# MCU_Peripherals.net
KiCad netlist of a schematic drawn in Altium Designer
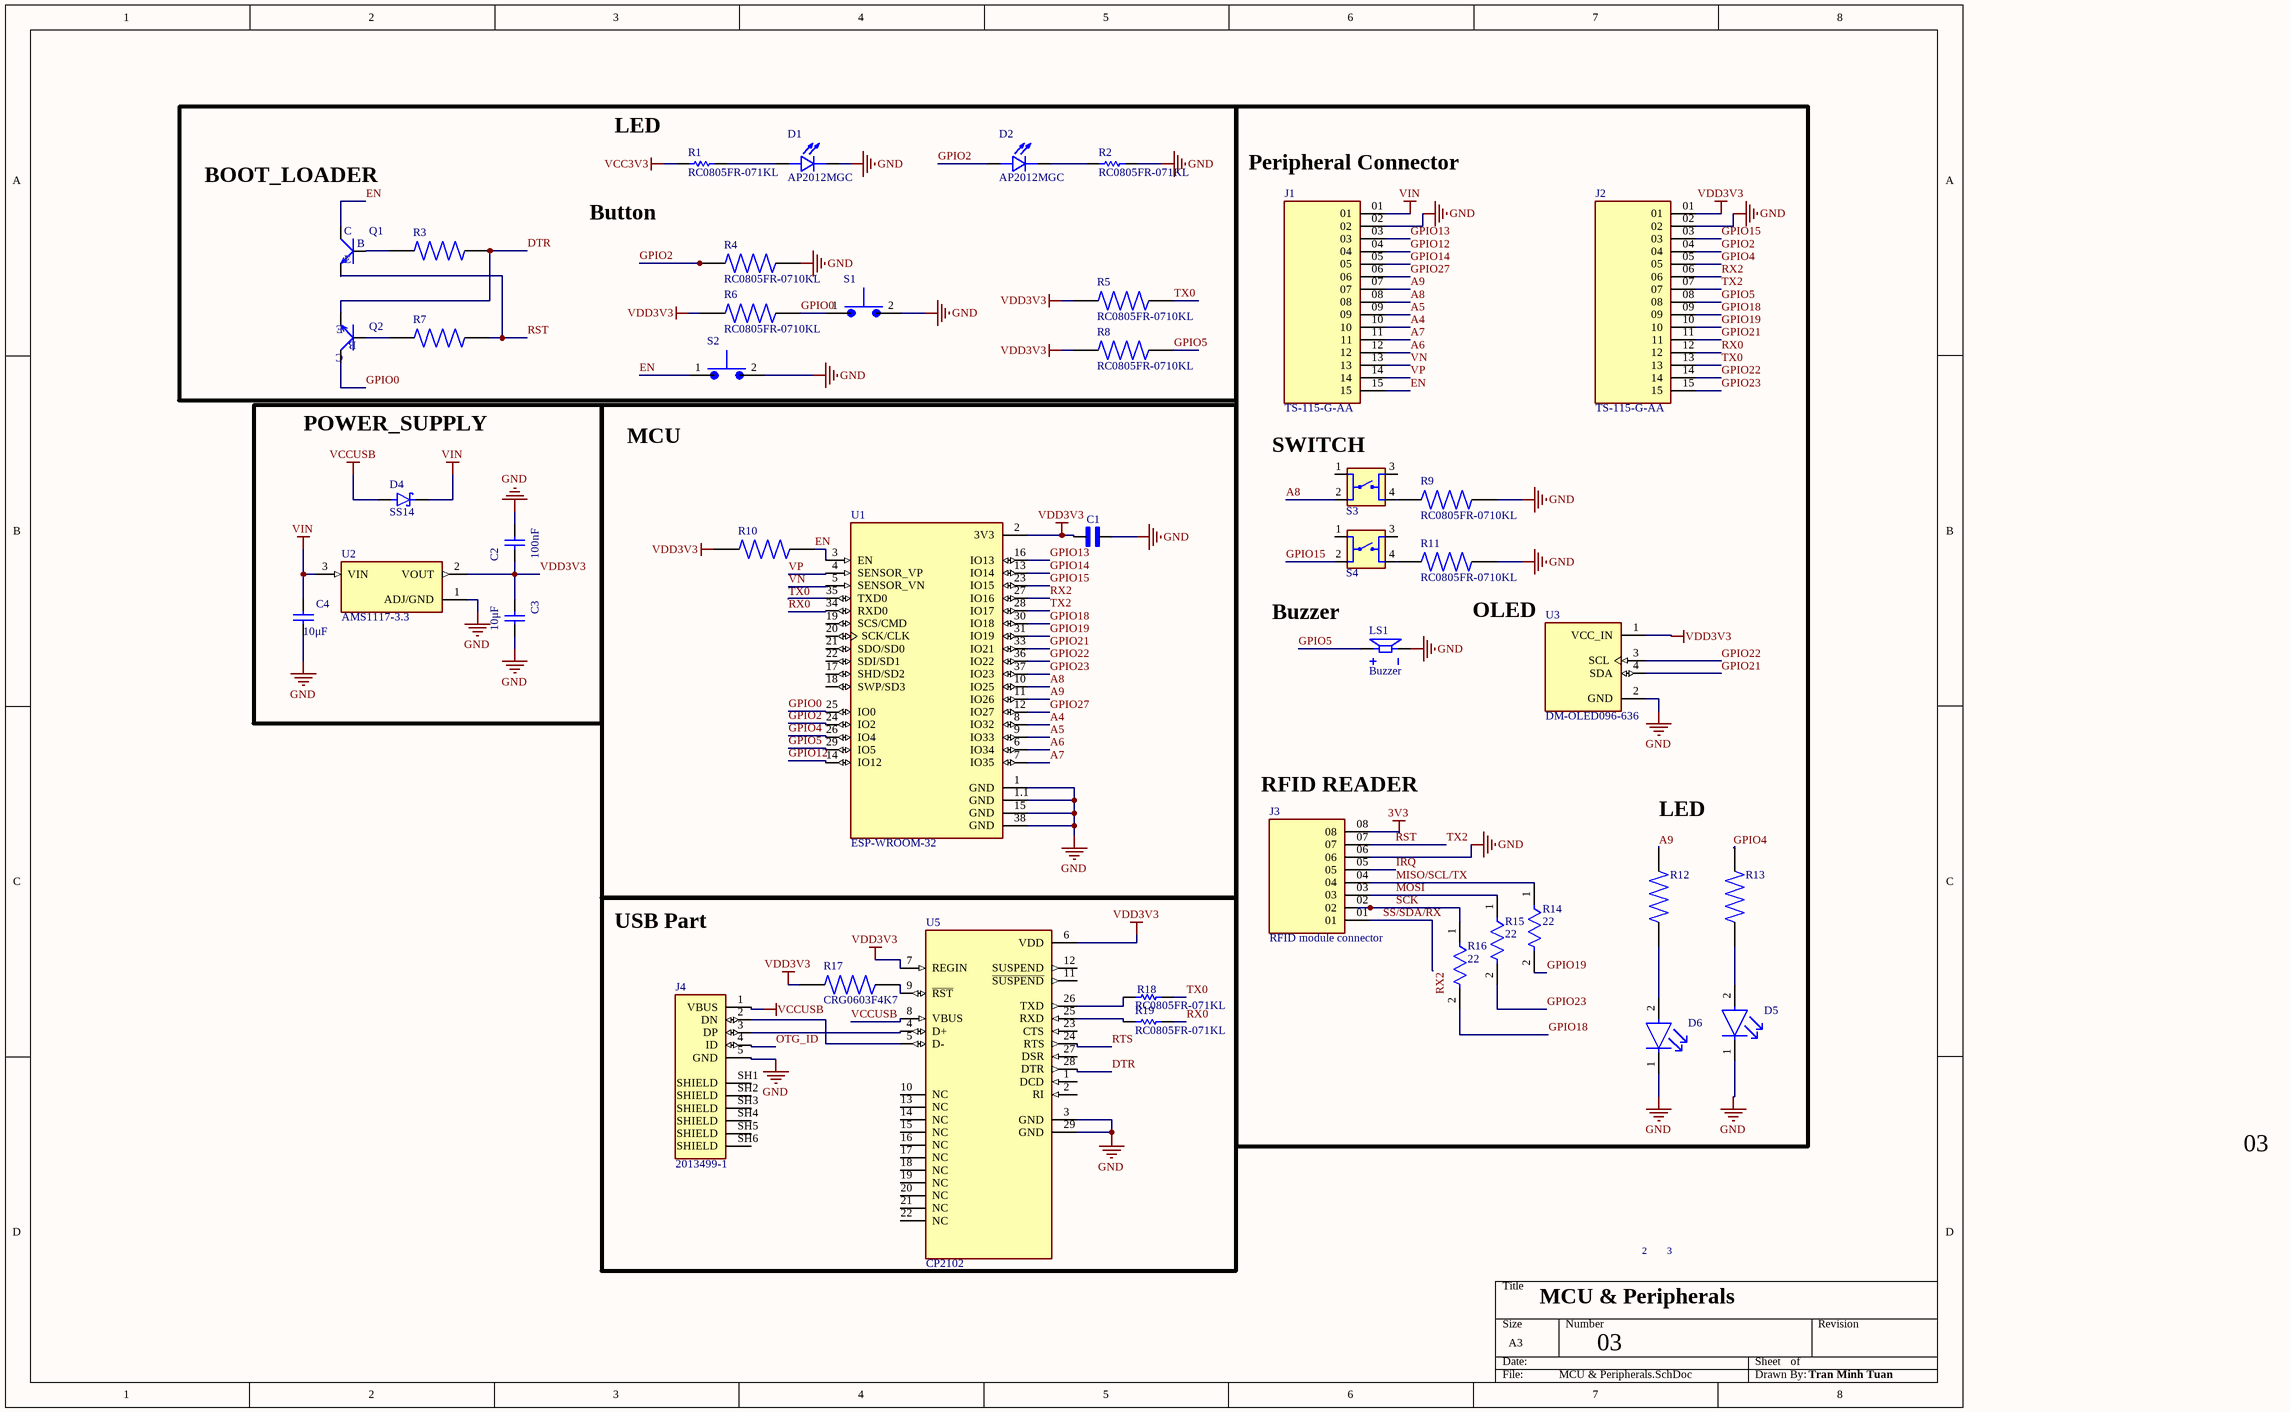
[diagram p0: MCU & Peripherals.SchDoc]

(export (version "E")
  (design (tool "Eeschema 10.0.6"))
  (components
    (comp (ref "C1")
      (value "GRM32EC70J107ME15L")
      (footprint "CAPC3225X270N")
      (description "SMD capacitor X7S(EIA) with capacitance 100uF Tol.20%. Rated voltage 6.3Vdc 125C")
      (fields (field (name "MF") "Murata Electronics"))
      (libsource (lib "Cap100uF") (part "GRM32EC70J107ME15L"))
    )
    (comp (ref "C2")
      (value "100nF")
      (footprint "WCAP-CSGP_0805_L2W1.25H0.8_Reflow")
      (description "WCAP-CSGP Multilayer Ceramic Chip Capacitor, General Purpose, size 0805, X7R, 100nF, 25V")
      (fields
        (field (name "MANUFACTURER PART NUMBER") "885012207072")
        (field (name "MANUFACTURER") "Wurth Elektronik")
      )
      (libsource (lib "Cap100n") (part "885012207072"))
    )
    (comp (ref "C3")
      (value "10μF")
      (footprint "WCAP-CSGP_0805_L2W1.25H1.25")
      (description "WCAP-CSGP Multilayer Ceramic Chip Capacitor, General Purpose, size 0805, X5R Class II, 10μF, 25V")
      (fields
        (field (name "MANUFACTURER PART NUMBER") "885012107027")
        (field (name "MANUFACTURER") "Wurth Elektronik")
      )
      (libsource (lib "Cap100n") (part "885012107027"))
    )
    (comp (ref "C4")
      (value "10μF")
      (footprint "WCAP-CSGP_0805_L2W1.25H1.25")
      (description "WCAP-CSGP Multilayer Ceramic Chip Capacitor, General Purpose, size 0805, X5R Class II, 10μF, 25V")
      (fields
        (field (name "MANUFACTURER PART NUMBER") "885012107027")
        (field (name "MANUFACTURER") "Wurth Elektronik")
      )
      (libsource (lib "Cap100n") (part "885012107027"))
    )
    (comp (ref "D1")
      (value "AP2012MGC")
      (footprint "LED_AP2012MGC")
      (description "Green 2 x 1.25 x 1.1 mm 120Â° Water Clear 70 mcd 2.1 V Chip LED Lamp SMT")
      (fields (field (name "MF") "Kingbright"))
      (libsource (lib "LED_GREEN") (part "AP2012MGC"))
    )
    (comp (ref "D2")
      (value "AP2012MGC")
      (footprint "LED_AP2012MGC")
      (description "Green 2 x 1.25 x 1.1 mm 120Â° Water Clear 70 mcd 2.1 V Chip LED Lamp SMT")
      (fields (field (name "MF") "Kingbright"))
      (libsource (lib "LED_GREEN") (part "AP2012MGC"))
    )
    (comp (ref "D4")
      (value "SS14")
      (footprint "DIOM4325X250N")
      (description "1A, 40V, Schottky Rectifier")
      (fields (field (name "MF") "Taiwan Semiconductor"))
      (libsource (lib "SS14") (part "SS14"))
    )
    (comp (ref "D5")
      (value "HLMP-1719")
      (footprint "FP-HLMP-1719-MFG")
      (description "LED YELLOW DIFFUSED T-1 T/H")
      (fields
        (field (name "MANUFACTURER") "Broadcom")
        (field (name "OCTOPART") "https://octopart.com/hlmp-1719-broadcom-71130405")
      )
      (libsource (lib "LED") (part "CMP-2000-06410-2"))
    )
    (comp (ref "D6")
      (value "HLMP-1719")
      (footprint "FP-HLMP-1719-MFG")
      (description "LED YELLOW DIFFUSED T-1 T/H")
      (fields
        (field (name "MANUFACTURER") "Broadcom")
        (field (name "OCTOPART") "https://octopart.com/hlmp-1719-broadcom-71130405")
      )
      (libsource (lib "LED") (part "CMP-2000-06410-2"))
    )
    (comp (ref "J1")
      (value "TS-115-G-AA")
      (footprint "SAMTEC_TS-115-G-AA")
      (fields (field (name "MF") "Samtec"))
      (libsource (lib "15x1 pin") (part "TS-115-G-AA"))
    )
    (comp (ref "J2")
      (value "TS-115-G-AA")
      (footprint "SAMTEC_TS-115-G-AA")
      (fields (field (name "MF") "Samtec"))
      (libsource (lib "15x1 pin") (part "TS-115-G-AA"))
    )
    (comp (ref "J3")
      (value "RFID module connector")
      (footprint "SAMTEC_SL-108-T-19")
      (fields (field (name "MP") "SL-108-T-19"))
      (libsource (lib "8 position connector") (part "SL-108-T-19"))
    )
    (comp (ref "J4")
      (value "2013499-1")
      (footprint "TE_2013499-1")
      (libsource (lib "Micro_USB") (part "2013499-1"))
    )
    (comp (ref "LS1")
      (value "Buzzer")
      (footprint "XDCR_CMI-1210-5-95T")
      (fields (field (name "MP") "CMI-1210-5-95T"))
      (libsource (lib "CMI-1210-5-95T") (part "CMI-1210-5-95T"))
    )
    (comp (ref "Q1")
      (value "SMD-TRANSISTORS-NPN-25V-500MW(SOT-23)")
      (footprint "SOT-23")
      (description "Bipolar (BJT) Transistor NPN 25 V 500 mA 150MHz 300 mW Surface Mount SOT-23")
      (fields (field (name "MF") "UMW") (field (name "MP") "S8050"))
      (libsource (lib "S8050") (part "SMD-TRANSISTORS-NPN-25V-500MW(SOT-23)"))
    )
    (comp (ref "Q2")
      (value "SMD-TRANSISTORS-NPN-25V-500MW(SOT-23)")
      (footprint "SOT-23")
      (description "Bipolar (BJT) Transistor NPN 25 V 500 mA 150MHz 300 mW Surface Mount SOT-23")
      (fields (field (name "MF") "UMW") (field (name "MP") "S8050"))
      (libsource (lib "S8050") (part "SMD-TRANSISTORS-NPN-25V-500MW(SOT-23)"))
    )
    (comp (ref "R1")
      (value "RC0805FR-071KL")
      (footprint "RESC2013X60X35NL10T20")
      (description "Chip Resistor, 1 KOhm, +/- 1%, 125 mW, -55 to 155 degC, 0805 (2012 Metric), RoHS, Tape and Reel")
      (fields (field (name "TOLERANCE") "1%") (field (name "MANUFACTURER") "Yageo"))
      (libsource (lib "RES1K") (part "CMP-2100-03671-1"))
    )
    (comp (ref "R2")
      (value "RC0805FR-071KL")
      (footprint "RESC2013X60X35NL10T20")
      (description "Chip Resistor, 1 KOhm, +/- 1%, 125 mW, -55 to 155 degC, 0805 (2012 Metric), RoHS, Tape and Reel")
      (fields (field (name "TOLERANCE") "1%") (field (name "MANUFACTURER") "Yageo"))
      (libsource (lib "RES1K") (part "CMP-2100-03671-1"))
    )
    (comp (ref "R3")
      (value "RC0805FR-0710KL")
      (footprint "RESC2012X60N")
      (description "10 kOhms Â±1% 0.125W, 1/8W Chip Resistor 0805 (2012 Metric) Moisture Resistant Thick Film")
      (fields (field (name "MF") "Yageo"))
      (libsource (lib "RES10k") (part "RC0805FR-0710KL"))
    )
    (comp (ref "R4")
      (value "RC0805FR-0710KL")
      (footprint "RESC2012X60N")
      (description "10 kOhms Â±1% 0.125W, 1/8W Chip Resistor 0805 (2012 Metric) Moisture Resistant Thick Film")
      (fields (field (name "MF") "Yageo"))
      (libsource (lib "RES10k") (part "RC0805FR-0710KL"))
    )
    (comp (ref "R5")
      (value "RC0805FR-0710KL")
      (footprint "RESC2012X60N")
      (description "10 kOhms Â±1% 0.125W, 1/8W Chip Resistor 0805 (2012 Metric) Moisture Resistant Thick Film")
      (fields (field (name "MF") "Yageo"))
      (libsource (lib "RES10k") (part "RC0805FR-0710KL"))
    )
    (comp (ref "R6")
      (value "RC0805FR-0710KL")
      (footprint "RESC2012X60N")
      (description "10 kOhms Â±1% 0.125W, 1/8W Chip Resistor 0805 (2012 Metric) Moisture Resistant Thick Film")
      (fields (field (name "MF") "Yageo"))
      (libsource (lib "RES10k") (part "RC0805FR-0710KL"))
    )
    (comp (ref "R7")
      (value "RC0805FR-0710KL")
      (footprint "RESC2012X60N")
      (description "10 kOhms Â±1% 0.125W, 1/8W Chip Resistor 0805 (2012 Metric) Moisture Resistant Thick Film")
      (fields (field (name "MF") "Yageo"))
      (libsource (lib "RES10k") (part "RC0805FR-0710KL"))
    )
    (comp (ref "R8")
      (value "RC0805FR-0710KL")
      (footprint "RESC2012X60N")
      (description "10 kOhms Â±1% 0.125W, 1/8W Chip Resistor 0805 (2012 Metric) Moisture Resistant Thick Film")
      (fields (field (name "MF") "Yageo"))
      (libsource (lib "RES10k") (part "RC0805FR-0710KL"))
    )
    (comp (ref "R9")
      (value "RC0805FR-0710KL")
      (footprint "RESC2012X60N")
      (description "10 kOhms Â±1% 0.125W, 1/8W Chip Resistor 0805 (2012 Metric) Moisture Resistant Thick Film")
      (fields (field (name "MF") "Yageo"))
      (libsource (lib "RES10k") (part "RC0805FR-0710KL"))
    )
    (comp (ref "R10")
      (value "RC0805FR-0710KL")
      (footprint "RESC2012X60N")
      (description "10 kOhms Â±1% 0.125W, 1/8W Chip Resistor 0805 (2012 Metric) Moisture Resistant Thick Film")
      (fields (field (name "MF") "Yageo"))
      (libsource (lib "RES10k") (part "RC0805FR-0710KL"))
    )
    (comp (ref "R11")
      (value "RC0805FR-0710KL")
      (footprint "RESC2012X60N")
      (description "10 kOhms Â±1% 0.125W, 1/8W Chip Resistor 0805 (2012 Metric) Moisture Resistant Thick Film")
      (fields (field (name "MF") "Yageo"))
      (libsource (lib "RES10k") (part "RC0805FR-0710KL"))
    )
    (comp (ref "R12")
      (value "ERJPA3F5100V")
      (footprint "RES_ERJPA3F5100V")
      (description "RES, THICK FILM, 510R, 1%, 0.25W, 0603")
      (fields (field (name "MF") "Panasonic") (field (name "MP") "ERJ-PA3F5100V"))
      (libsource (lib "RES510") (part "ERJPA3F5100V"))
    )
    (comp (ref "R13")
      (value "ERJPA3F5100V")
      (footprint "RES_ERJPA3F5100V")
      (description "RES, THICK FILM, 510R, 1%, 0.25W, 0603")
      (fields (field (name "MF") "Panasonic") (field (name "MP") "ERJ-PA3F5100V"))
      (libsource (lib "RES510") (part "ERJPA3F5100V"))
    )
    (comp (ref "R14")
      (value "22")
      (footprint "FP-ERJ3G-MFG")
      (description "RES SMD 22 OHM 5% 1/10W 0603")
      (fields (field (name "TOLERANCE") "5%"))
      (libsource (lib "RES22") (part "CMP-2000-00745-2"))
    )
    (comp (ref "R15")
      (value "22")
      (footprint "FP-ERJ3G-MFG")
      (description "RES SMD 22 OHM 5% 1/10W 0603")
      (fields (field (name "TOLERANCE") "5%"))
      (libsource (lib "RES22") (part "CMP-2000-00745-2"))
    )
    (comp (ref "R16")
      (value "22")
      (footprint "FP-ERJ3G-MFG")
      (description "RES SMD 22 OHM 5% 1/10W 0603")
      (fields (field (name "TOLERANCE") "5%"))
      (libsource (lib "RES22") (part "CMP-2000-00745-2"))
    )
    (comp (ref "R17")
      (value "CRG0603F4K7")
      (footprint "RESC1608X55N")
      (fields (field (name "MF") "TE Connectivity") (field (name "TOLERANCE") "1%"))
      (libsource (lib "RES4.7k") (part "CRG0603F4K7"))
    )
    (comp (ref "R18")
      (value "RC0805FR-071KL")
      (footprint "RESC2013X60X35NL10T20")
      (description "Chip Resistor, 1 KOhm, +/- 1%, 125 mW, -55 to 155 degC, 0805 (2012 Metric), RoHS, Tape and Reel")
      (fields (field (name "TOLERANCE") "1%") (field (name "MANUFACTURER") "Yageo"))
      (libsource (lib "RES1K") (part "CMP-2100-03671-1"))
    )
    (comp (ref "R19")
      (value "RC0805FR-071KL")
      (footprint "RESC2013X60X35NL10T20")
      (description "Chip Resistor, 1 KOhm, +/- 1%, 125 mW, -55 to 155 degC, 0805 (2012 Metric), RoHS, Tape and Reel")
      (fields (field (name "TOLERANCE") "1%") (field (name "MANUFACTURER") "Yageo"))
      (libsource (lib "RES1K") (part "CMP-2100-03671-1"))
    )
    (comp (ref "S1")
      (value "TS10-63-26-BE-250-SMT-TR")
      (footprint "SW_TS10-63-26-BE-250-SMT-TR")
      (description "6.1 x 3.8 mm, 2.6 mm Actuator Height, 250 gf, Surface Mount, SPST, Tactile Switch")
      (fields (field (name "MF") "Same Sky"))
      (libsource (lib "Switch") (part "TS10-63-26-BE-250-SMT-TR"))
    )
    (comp (ref "S2")
      (value "TS10-63-26-BE-250-SMT-TR")
      (footprint "SW_TS10-63-26-BE-250-SMT-TR")
      (description "6.1 x 3.8 mm, 2.6 mm Actuator Height, 250 gf, Surface Mount, SPST, Tactile Switch")
      (fields (field (name "MF") "Same Sky"))
      (libsource (lib "Switch") (part "TS10-63-26-BE-250-SMT-TR"))
    )
    (comp (ref "S3")
      (value "FSM8JH")
      (footprint "SW_FSM8JH")
      (description "Tactile Switch SPST-NO Top Actuated Through Hole")
      (fields (field (name "MF") "TE Connectivity"))
      (libsource (lib "Button") (part "FSM8JH"))
    )
    (comp (ref "S4")
      (value "FSM8JH")
      (footprint "SW_FSM8JH")
      (description "Tactile Switch SPST-NO Top Actuated Through Hole")
      (fields (field (name "MF") "TE Connectivity"))
      (libsource (lib "Button") (part "FSM8JH"))
    )
    (comp (ref "U1")
      (value "ESP-WROOM-32")
      (footprint "MODULE_ESP-WROOM-32")
      (fields (field (name "MF") "Espressif Systems"))
      (libsource (lib "ESP-WROOM-32") (part "ESP-WROOM-32"))
    )
    (comp (ref "U2")
      (value "AMS1117-3.3")
      (footprint "SOT229P700X180-4N")
      (description "Linear Voltage Regulator IC Positive Fixed 1 Output 1A SOT-223-3L")
      (fields (field (name "MF") "UMW"))
      (libsource (lib "AMS1117-3.3") (part "AMS1117-3.3"))
    )
    (comp (ref "U3")
      (value "DM-OLED096-636")
      (footprint "MODULE_DM-OLED096-636")
      (description "0.96â€ 128 X 64 MONOCHROME GRAPHIC OLED DISPLAY MODULE - I2C")
      (fields (field (name "MF") "Display Module"))
      (libsource (lib "DM-OLED096-636") (part "DM-OLED096-636"))
    )
    (comp (ref "U5")
      (value "CP2102")
      (footprint "QFN50P500X500X100-29N")
      (description "CP2102N USB 2.0 to UART (RS232) Bridge Interface Evaluation Board")
      (fields (field (name "MF") "Silicon Labs"))
      (libsource (lib "CP2102") (part "CP2102"))
    )
  )
  (nets
    (net (code "1") (name "/A4") (class "Default")
      (node (ref "J1") (pin "10") (pinfunction "10_10") (pintype "passive"))
      (node (ref "U1") (pin "8") (pinfunction "IO32_8") (pintype "bidirectional"))
    )
    (net (code "2") (name "/A5") (class "Default")
      (node (ref "J1") (pin "09") (pinfunction "09_09") (pintype "passive"))
      (node (ref "U1") (pin "9") (pinfunction "IO33_9") (pintype "bidirectional"))
    )
    (net (code "3") (name "/A6") (class "Default")
      (node (ref "J1") (pin "12") (pinfunction "12_12") (pintype "passive"))
      (node (ref "U1") (pin "6") (pinfunction "IO34_6") (pintype "bidirectional"))
    )
    (net (code "4") (name "/A7") (class "Default")
      (node (ref "J1") (pin "11") (pinfunction "11_11") (pintype "passive"))
      (node (ref "U1") (pin "7") (pinfunction "IO35_7") (pintype "bidirectional"))
    )
    (net (code "5") (name "/A8") (class "Default")
      (node (ref "J1") (pin "08") (pinfunction "08_08") (pintype "passive"))
      (node (ref "S3") (pin "2") (pinfunction "2_2") (pintype "passive"))
      (node (ref "U1") (pin "10") (pinfunction "IO25_10") (pintype "bidirectional"))
    )
    (net (code "6") (name "/A9") (class "Default")
      (node (ref "J1") (pin "07") (pinfunction "07_07") (pintype "passive"))
      (node (ref "R12") (pin "1") (pinfunction "1_1") (pintype "passive"))
      (node (ref "U1") (pin "11") (pinfunction "IO26_11") (pintype "bidirectional"))
    )
    (net (code "7") (name "/DTR") (class "Default")
      (node (ref "Q2") (pin "2") (pinfunction "E_2") (pintype "passive"))
      (node (ref "R3") (pin "2") (pinfunction "2_2") (pintype "passive"))
      (node (ref "U5") (pin "28") (pinfunction "DTR_28") (pintype "output"))
    )
    (net (code "8") (name "/EN") (class "Default")
      (node (ref "J1") (pin "15") (pinfunction "15_15") (pintype "passive"))
      (node (ref "Q1") (pin "3") (pinfunction "C_3") (pintype "passive"))
      (node (ref "R10") (pin "2") (pinfunction "2_2") (pintype "passive"))
      (node (ref "S2") (pin "1") (pinfunction "1_1") (pintype "passive"))
      (node (ref "U1") (pin "3") (pinfunction "EN_3") (pintype "input"))
    )
    (net (code "9") (name "/GPIO0") (class "Default")
      (node (ref "Q2") (pin "3") (pinfunction "C_3") (pintype "passive"))
      (node (ref "R6") (pin "2") (pinfunction "2_2") (pintype "passive"))
      (node (ref "S1") (pin "1") (pinfunction "1_1") (pintype "passive"))
      (node (ref "U1") (pin "25") (pinfunction "IO0_25") (pintype "bidirectional"))
    )
    (net (code "10") (name "/GPIO2") (class "Default")
      (node (ref "D2") (pin "A") (pinfunction "A_A") (pintype "passive"))
      (node (ref "J2") (pin "04") (pinfunction "04_04") (pintype "passive"))
      (node (ref "R4") (pin "1") (pinfunction "1_1") (pintype "passive"))
      (node (ref "U1") (pin "24") (pinfunction "IO2_24") (pintype "bidirectional"))
    )
    (net (code "11") (name "/GPIO4") (class "Default")
      (node (ref "J2") (pin "05") (pinfunction "05_05") (pintype "passive"))
      (node (ref "R13") (pin "1") (pinfunction "1_1") (pintype "passive"))
      (node (ref "U1") (pin "26") (pinfunction "IO4_26") (pintype "bidirectional"))
    )
    (net (code "12") (name "/GPIO5") (class "Default")
      (node (ref "J2") (pin "08") (pinfunction "08_08") (pintype "passive"))
      (node (ref "LS1") (pin "P") (pinfunction "P_P") (pintype "passive"))
      (node (ref "R8") (pin "2") (pinfunction "2_2") (pintype "passive"))
      (node (ref "U1") (pin "29") (pinfunction "IO5_29") (pintype "bidirectional"))
    )
    (net (code "13") (name "/GPIO12") (class "Default")
      (node (ref "J1") (pin "04") (pinfunction "04_04") (pintype "passive"))
      (node (ref "U1") (pin "14") (pinfunction "IO12_14") (pintype "bidirectional"))
    )
    (net (code "14") (name "/GPIO13") (class "Default")
      (node (ref "J1") (pin "03") (pinfunction "03_03") (pintype "passive"))
      (node (ref "U1") (pin "16") (pinfunction "IO13_16") (pintype "bidirectional"))
    )
    (net (code "15") (name "/GPIO14") (class "Default")
      (node (ref "J1") (pin "05") (pinfunction "05_05") (pintype "passive"))
      (node (ref "U1") (pin "13") (pinfunction "IO14_13") (pintype "bidirectional"))
    )
    (net (code "16") (name "/GPIO15") (class "Default")
      (node (ref "J2") (pin "03") (pinfunction "03_03") (pintype "passive"))
      (node (ref "S4") (pin "2") (pinfunction "2_2") (pintype "passive"))
      (node (ref "U1") (pin "23") (pinfunction "IO15_23") (pintype "bidirectional"))
    )
    (net (code "17") (name "/GPIO18") (class "Default")
      (node (ref "J2") (pin "09") (pinfunction "09_09") (pintype "passive"))
      (node (ref "R16") (pin "2") (pinfunction "2_2") (pintype "passive"))
      (node (ref "U1") (pin "30") (pinfunction "IO18_30") (pintype "bidirectional"))
    )
    (net (code "18") (name "/GPIO19") (class "Default")
      (node (ref "J2") (pin "10") (pinfunction "10_10") (pintype "passive"))
      (node (ref "R14") (pin "2") (pinfunction "2_2") (pintype "passive"))
      (node (ref "U1") (pin "31") (pinfunction "IO19_31") (pintype "bidirectional"))
    )
    (net (code "19") (name "/GPIO21") (class "Default")
      (node (ref "J2") (pin "11") (pinfunction "11_11") (pintype "passive"))
      (node (ref "U1") (pin "33") (pinfunction "IO21_33") (pintype "bidirectional"))
      (node (ref "U3") (pin "4") (pinfunction "SDA_4") (pintype "bidirectional"))
    )
    (net (code "20") (name "/GPIO22") (class "Default")
      (node (ref "J2") (pin "14") (pinfunction "14_14") (pintype "passive"))
      (node (ref "U1") (pin "36") (pinfunction "IO22_36") (pintype "bidirectional"))
      (node (ref "U3") (pin "3") (pinfunction "SCL_3") (pintype "input"))
    )
    (net (code "21") (name "/GPIO23") (class "Default")
      (node (ref "J2") (pin "15") (pinfunction "15_15") (pintype "passive"))
      (node (ref "R15") (pin "2") (pinfunction "2_2") (pintype "passive"))
      (node (ref "U1") (pin "37") (pinfunction "IO23_37") (pintype "bidirectional"))
    )
    (net (code "22") (name "/GPIO27") (class "Default")
      (node (ref "J1") (pin "06") (pinfunction "06_06") (pintype "passive"))
      (node (ref "U1") (pin "12") (pinfunction "IO27_12") (pintype "bidirectional"))
    )
    (net (code "23") (name "/IRQ") (class "Default")
      (node (ref "J3") (pin "05") (pinfunction "05_05") (pintype "passive"))
    )
    (net (code "24") (name "/MISO{slash}SCL{slash}TX") (class "Default")
      (node (ref "J3") (pin "04") (pinfunction "04_04") (pintype "passive"))
      (node (ref "R14") (pin "1") (pinfunction "1_1") (pintype "passive"))
    )
    (net (code "25") (name "/MOSI") (class "Default")
      (node (ref "J3") (pin "03") (pinfunction "03_03") (pintype "passive"))
      (node (ref "R15") (pin "1") (pinfunction "1_1") (pintype "passive"))
    )
    (net (code "26") (name "/OTG_ID") (class "Default")
      (node (ref "J4") (pin "4") (pinfunction "ID_4") (pintype "bidirectional"))
    )
    (net (code "27") (name "/RST") (class "Default")
      (node (ref "J2") (pin "07") (pinfunction "07_07") (pintype "passive"))
      (node (ref "J3") (pin "07") (pinfunction "07_07") (pintype "passive"))
      (node (ref "Q1") (pin "2") (pinfunction "E_2") (pintype "passive"))
      (node (ref "R7") (pin "2") (pinfunction "2_2") (pintype "passive"))
      (node (ref "U1") (pin "28") (pinfunction "IO17_28") (pintype "bidirectional"))
    )
    (net (code "28") (name "/RTS") (class "Default")
      (node (ref "U5") (pin "24") (pinfunction "RTS_24") (pintype "output"))
    )
    (net (code "29") (name "/RX0") (class "Default")
      (node (ref "J2") (pin "12") (pinfunction "12_12") (pintype "passive"))
      (node (ref "R19") (pin "2") (pinfunction "2_2") (pintype "passive"))
      (node (ref "U1") (pin "34") (pinfunction "RXD0_34") (pintype "bidirectional"))
    )
    (net (code "30") (name "/RX2") (class "Default")
      (node (ref "J2") (pin "06") (pinfunction "06_06") (pintype "passive"))
      (node (ref "J3") (pin "01") (pinfunction "01_01") (pintype "passive"))
      (node (ref "U1") (pin "27") (pinfunction "IO16_27") (pintype "bidirectional"))
    )
    (net (code "31") (name "/SCK") (class "Default")
      (node (ref "J3") (pin "02") (pinfunction "02_02") (pintype "passive"))
      (node (ref "R16") (pin "1") (pinfunction "1_1") (pintype "passive"))
    )
    (net (code "32") (name "/TX0") (class "Default")
      (node (ref "J2") (pin "13") (pinfunction "13_13") (pintype "passive"))
      (node (ref "R18") (pin "2") (pinfunction "2_2") (pintype "passive"))
      (node (ref "R5") (pin "2") (pinfunction "2_2") (pintype "passive"))
      (node (ref "U1") (pin "35") (pinfunction "TXD0_35") (pintype "bidirectional"))
    )
    (net (code "33") (name "/VN") (class "Default")
      (node (ref "J1") (pin "13") (pinfunction "13_13") (pintype "passive"))
      (node (ref "U1") (pin "5") (pinfunction "SENSOR_VN_5") (pintype "input"))
    )
    (net (code "34") (name "/VP") (class "Default")
      (node (ref "J1") (pin "14") (pinfunction "14_14") (pintype "passive"))
      (node (ref "U1") (pin "4") (pinfunction "SENSOR_VP_4") (pintype "input"))
    )
    (net (code "35") (name "3V3") (class "Default")
      (node (ref "J3") (pin "08") (pinfunction "08_08") (pintype "passive"))
    )
    (net (code "36") (name "GND") (class "Default")
      (node (ref "C1") (pin "2") (pinfunction "2_2") (pintype "passive"))
      (node (ref "C2") (pin "2") (pinfunction "2_2") (pintype "passive"))
      (node (ref "C3") (pin "2") (pinfunction "2_2") (pintype "passive"))
      (node (ref "C4") (pin "2") (pinfunction "2_2") (pintype "passive"))
      (node (ref "D1") (pin "C") (pinfunction "C_C") (pintype "passive"))
      (node (ref "D5") (pin "1") (pinfunction "C_1") (pintype "passive"))
      (node (ref "D6") (pin "1") (pinfunction "C_1") (pintype "passive"))
      (node (ref "J1") (pin "02") (pinfunction "02_02") (pintype "passive"))
      (node (ref "J2") (pin "02") (pinfunction "02_02") (pintype "passive"))
      (node (ref "J3") (pin "06") (pinfunction "06_06") (pintype "passive"))
      (node (ref "J4") (pin "5") (pinfunction "GND_5") (pintype "power_in"))
      (node (ref "LS1") (pin "N") (pinfunction "N_N") (pintype "passive"))
      (node (ref "R11") (pin "1") (pinfunction "1_1") (pintype "passive"))
      (node (ref "R2") (pin "2") (pinfunction "2_2") (pintype "passive"))
      (node (ref "R4") (pin "2") (pinfunction "2_2") (pintype "passive"))
      (node (ref "R9") (pin "1") (pinfunction "1_1") (pintype "passive"))
      (node (ref "S1") (pin "2") (pinfunction "2_2") (pintype "passive"))
      (node (ref "S2") (pin "2") (pinfunction "2_2") (pintype "passive"))
      (node (ref "U1") (pin "1") (pinfunction "GND_1") (pintype "power_in"))
      (node (ref "U1") (pin "1.1") (pinfunction "GND_1.1") (pintype "power_in"))
      (node (ref "U1") (pin "15") (pinfunction "GND_15") (pintype "power_in"))
      (node (ref "U1") (pin "38") (pinfunction "GND_38") (pintype "power_in"))
      (node (ref "U2") (pin "1") (pinfunction "ADJ/GND_1") (pintype "power_in"))
      (node (ref "U3") (pin "2") (pinfunction "GND_2") (pintype "power_in"))
      (node (ref "U5") (pin "29") (pinfunction "GND_29") (pintype "power_in"))
      (node (ref "U5") (pin "3") (pinfunction "GND_3") (pintype "power_in"))
    )
    (net (code "37") (name "Net-(D1-PadA)") (class "Default")
      (node (ref "D1") (pin "A") (pinfunction "A_A") (pintype "passive"))
      (node (ref "R1") (pin "2") (pinfunction "2_2") (pintype "passive"))
    )
    (net (code "38") (name "Net-(D2-PadC)") (class "Default")
      (node (ref "D2") (pin "C") (pinfunction "C_C") (pintype "passive"))
      (node (ref "R2") (pin "1") (pinfunction "1_1") (pintype "passive"))
    )
    (net (code "39") (name "Net-(D5-A)") (class "Default")
      (node (ref "D5") (pin "2") (pinfunction "A_2") (pintype "passive"))
      (node (ref "R13") (pin "2") (pinfunction "2_2") (pintype "passive"))
    )
    (net (code "40") (name "Net-(D6-A)") (class "Default")
      (node (ref "D6") (pin "2") (pinfunction "A_2") (pintype "passive"))
      (node (ref "R12") (pin "2") (pinfunction "2_2") (pintype "passive"))
    )
    (net (code "41") (name "Net-(J4-DN)") (class "Default")
      (node (ref "J4") (pin "2") (pinfunction "DN_2") (pintype "bidirectional"))
      (node (ref "U5") (pin "5") (pinfunction "D-_5") (pintype "bidirectional"))
    )
    (net (code "42") (name "Net-(J4-DP)") (class "Default")
      (node (ref "J4") (pin "3") (pinfunction "DP_3") (pintype "bidirectional"))
      (node (ref "U5") (pin "4") (pinfunction "D+_4") (pintype "bidirectional"))
    )
    (net (code "43") (name "Net-(Q1-B)") (class "Default")
      (node (ref "Q1") (pin "1") (pinfunction "B_1") (pintype "passive"))
      (node (ref "R3") (pin "1") (pinfunction "1_1") (pintype "passive"))
    )
    (net (code "44") (name "Net-(Q2-B)") (class "Default")
      (node (ref "Q2") (pin "1") (pinfunction "B_1") (pintype "passive"))
      (node (ref "R7") (pin "1") (pinfunction "1_1") (pintype "passive"))
    )
    (net (code "45") (name "Net-(R9-Pad2)") (class "Default")
      (node (ref "R9") (pin "2") (pinfunction "2_2") (pintype "passive"))
      (node (ref "S3") (pin "4") (pinfunction "4_4") (pintype "passive"))
    )
    (net (code "46") (name "Net-(R11-Pad2)") (class "Default")
      (node (ref "R11") (pin "2") (pinfunction "2_2") (pintype "passive"))
      (node (ref "S4") (pin "4") (pinfunction "4_4") (pintype "passive"))
    )
    (net (code "47") (name "Net-(U5-RXD)") (class "Default")
      (node (ref "R19") (pin "1") (pinfunction "1_1") (pintype "passive"))
      (node (ref "U5") (pin "25") (pinfunction "RXD_25") (pintype "input"))
    )
    (net (code "48") (name "Net-(U5-TXD)") (class "Default")
      (node (ref "R18") (pin "1") (pinfunction "1_1") (pintype "passive"))
      (node (ref "U5") (pin "26") (pinfunction "TXD_26") (pintype "output"))
    )
    (net (code "49") (name "Net-(U5-~{RST})") (class "Default")
      (node (ref "R17") (pin "2") (pinfunction "2_2") (pintype "passive"))
      (node (ref "U5") (pin "9") (pinfunction "~{RST}_9") (pintype "bidirectional"))
    )
    (net (code "50") (name "VCC3V3") (class "Default")
      (node (ref "R1") (pin "1") (pinfunction "1_1") (pintype "passive"))
    )
    (net (code "51") (name "VCCUSB") (class "Default")
      (node (ref "D4") (pin "A") (pinfunction "A_A") (pintype "passive"))
      (node (ref "J4") (pin "1") (pinfunction "VBUS_1") (pintype "power_in"))
      (node (ref "U5") (pin "8") (pinfunction "VBUS_8") (pintype "input"))
    )
    (net (code "52") (name "VDD3V3") (class "Default")
      (node (ref "C1") (pin "1") (pinfunction "1_1") (pintype "passive"))
      (node (ref "C2") (pin "1") (pinfunction "1_1") (pintype "passive"))
      (node (ref "C3") (pin "1") (pinfunction "1_1") (pintype "passive"))
      (node (ref "J2") (pin "01") (pinfunction "01_01") (pintype "passive"))
      (node (ref "R10") (pin "1") (pinfunction "1_1") (pintype "passive"))
      (node (ref "R17") (pin "1") (pinfunction "1_1") (pintype "passive"))
      (node (ref "R5") (pin "1") (pinfunction "1_1") (pintype "passive"))
      (node (ref "R6") (pin "1") (pinfunction "1_1") (pintype "passive"))
      (node (ref "R8") (pin "1") (pinfunction "1_1") (pintype "passive"))
      (node (ref "U1") (pin "2") (pinfunction "3V3_2") (pintype "power_in"))
      (node (ref "U2") (pin "2") (pinfunction "VOUT_2") (pintype "output"))
      (node (ref "U3") (pin "1") (pinfunction "VCC_IN_1") (pintype "power_in"))
      (node (ref "U5") (pin "6") (pinfunction "VDD_6") (pintype "power_in"))
      (node (ref "U5") (pin "7") (pinfunction "REGIN_7") (pintype "input"))
    )
    (net (code "53") (name "VIN") (class "Default")
      (node (ref "C4") (pin "1") (pinfunction "1_1") (pintype "passive"))
      (node (ref "D4") (pin "C") (pinfunction "K_C") (pintype "passive"))
      (node (ref "J1") (pin "01") (pinfunction "01_01") (pintype "passive"))
      (node (ref "U2") (pin "3") (pinfunction "VIN_3") (pintype "input"))
    )
    (net (code "54") (name "unconnected-(J4-SHIELD-PadSH1)") (class "Default")
      (node (ref "J4") (pin "SH1") (pinfunction "SHIELD_SH1") (pintype "passive"))
    )
    (net (code "55") (name "unconnected-(J4-SHIELD-PadSH2)") (class "Default")
      (node (ref "J4") (pin "SH2") (pinfunction "SHIELD_SH2") (pintype "passive"))
    )
    (net (code "56") (name "unconnected-(J4-SHIELD-PadSH3)") (class "Default")
      (node (ref "J4") (pin "SH3") (pinfunction "SHIELD_SH3") (pintype "passive"))
    )
    (net (code "57") (name "unconnected-(J4-SHIELD-PadSH4)") (class "Default")
      (node (ref "J4") (pin "SH4") (pinfunction "SHIELD_SH4") (pintype "passive"))
    )
    (net (code "58") (name "unconnected-(J4-SHIELD-PadSH5)") (class "Default")
      (node (ref "J4") (pin "SH5") (pinfunction "SHIELD_SH5") (pintype "passive"))
    )
    (net (code "59") (name "unconnected-(J4-SHIELD-PadSH6)") (class "Default")
      (node (ref "J4") (pin "SH6") (pinfunction "SHIELD_SH6") (pintype "passive"))
    )
    (net (code "60") (name "unconnected-(S3-Pad1)") (class "Default")
      (node (ref "S3") (pin "1") (pinfunction "1_1") (pintype "passive"))
    )
    (net (code "61") (name "unconnected-(S3-Pad3)") (class "Default")
      (node (ref "S3") (pin "3") (pinfunction "3_3") (pintype "passive"))
    )
    (net (code "62") (name "unconnected-(S4-Pad1)") (class "Default")
      (node (ref "S4") (pin "1") (pinfunction "1_1") (pintype "passive"))
    )
    (net (code "63") (name "unconnected-(S4-Pad3)") (class "Default")
      (node (ref "S4") (pin "3") (pinfunction "3_3") (pintype "passive"))
    )
    (net (code "64") (name "unconnected-(U1-SCK{slash}CLK-Pad20)") (class "Default")
      (node (ref "U1") (pin "20") (pinfunction "SCK/CLK_20") (pintype "bidirectional"))
    )
    (net (code "65") (name "unconnected-(U1-SCS{slash}CMD-Pad19)") (class "Default")
      (node (ref "U1") (pin "19") (pinfunction "SCS/CMD_19") (pintype "bidirectional"))
    )
    (net (code "66") (name "unconnected-(U1-SDI{slash}SD1-Pad22)") (class "Default")
      (node (ref "U1") (pin "22") (pinfunction "SDI/SD1_22") (pintype "bidirectional"))
    )
    (net (code "67") (name "unconnected-(U1-SDO{slash}SD0-Pad21)") (class "Default")
      (node (ref "U1") (pin "21") (pinfunction "SDO/SD0_21") (pintype "bidirectional"))
    )
    (net (code "68") (name "unconnected-(U1-SHD{slash}SD2-Pad17)") (class "Default")
      (node (ref "U1") (pin "17") (pinfunction "SHD/SD2_17") (pintype "bidirectional"))
    )
    (net (code "69") (name "unconnected-(U1-SWP{slash}SD3-Pad18)") (class "Default")
      (node (ref "U1") (pin "18") (pinfunction "SWP/SD3_18") (pintype "bidirectional"))
    )
    (net (code "70") (name "unconnected-(U5-CTS-Pad23)") (class "Default")
      (node (ref "U5") (pin "23") (pinfunction "CTS_23") (pintype "input"))
    )
    (net (code "71") (name "unconnected-(U5-DCD-Pad1)") (class "Default")
      (node (ref "U5") (pin "1") (pinfunction "DCD_1") (pintype "input"))
    )
    (net (code "72") (name "unconnected-(U5-DSR-Pad27)") (class "Default")
      (node (ref "U5") (pin "27") (pinfunction "DSR_27") (pintype "input"))
    )
    (net (code "73") (name "unconnected-(U5-NC-Pad10)") (class "Default")
      (node (ref "U5") (pin "10") (pinfunction "NC_10") (pintype "passive"))
    )
    (net (code "74") (name "unconnected-(U5-NC-Pad13)") (class "Default")
      (node (ref "U5") (pin "13") (pinfunction "NC_13") (pintype "passive"))
    )
    (net (code "75") (name "unconnected-(U5-NC-Pad14)") (class "Default")
      (node (ref "U5") (pin "14") (pinfunction "NC_14") (pintype "passive"))
    )
    (net (code "76") (name "unconnected-(U5-NC-Pad15)") (class "Default")
      (node (ref "U5") (pin "15") (pinfunction "NC_15") (pintype "passive"))
    )
    (net (code "77") (name "unconnected-(U5-NC-Pad16)") (class "Default")
      (node (ref "U5") (pin "16") (pinfunction "NC_16") (pintype "passive"))
    )
    (net (code "78") (name "unconnected-(U5-NC-Pad17)") (class "Default")
      (node (ref "U5") (pin "17") (pinfunction "NC_17") (pintype "passive"))
    )
    (net (code "79") (name "unconnected-(U5-NC-Pad18)") (class "Default")
      (node (ref "U5") (pin "18") (pinfunction "NC_18") (pintype "passive"))
    )
    (net (code "80") (name "unconnected-(U5-NC-Pad19)") (class "Default")
      (node (ref "U5") (pin "19") (pinfunction "NC_19") (pintype "passive"))
    )
    (net (code "81") (name "unconnected-(U5-NC-Pad20)") (class "Default")
      (node (ref "U5") (pin "20") (pinfunction "NC_20") (pintype "passive"))
    )
    (net (code "82") (name "unconnected-(U5-NC-Pad21)") (class "Default")
      (node (ref "U5") (pin "21") (pinfunction "NC_21") (pintype "passive"))
    )
    (net (code "83") (name "unconnected-(U5-NC-Pad22)") (class "Default")
      (node (ref "U5") (pin "22") (pinfunction "NC_22") (pintype "passive"))
    )
    (net (code "84") (name "unconnected-(U5-RI-Pad2)") (class "Default")
      (node (ref "U5") (pin "2") (pinfunction "RI_2") (pintype "input"))
    )
    (net (code "85") (name "unconnected-(U5-SUSPEND-Pad12)") (class "Default")
      (node (ref "U5") (pin "12") (pinfunction "SUSPEND_12") (pintype "output"))
    )
    (net (code "86") (name "unconnected-(U5-~{SUSPEND}-Pad11)") (class "Default")
      (node (ref "U5") (pin "11") (pinfunction "~{SUSPEND}_11") (pintype "output"))
    )
  )
)
